# Single_Side_Filter.net
KiCad netlist of a schematic drawn in Altium Designer
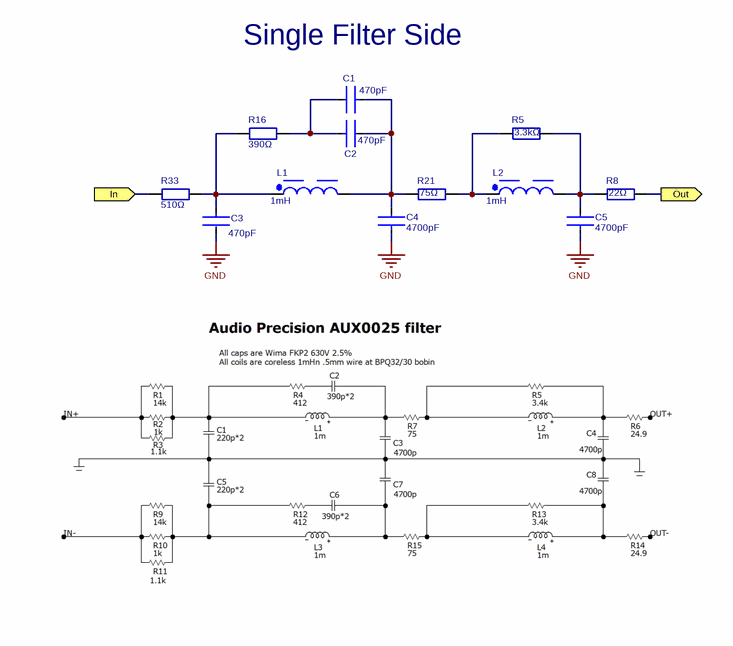
[diagram p0: Single Side Filter.SchDoc]

(export (version "E")
  (design (tool "Eeschema 10.0.6"))
  (components
    (comp (ref "C1")
      (value "470pF")
      (footprint "Film Capacitor 7.2 x 4.5 x 6.0 mm")
      (description "PFR5102F100J11L4BULK Cap Film 0.001uF 100V PP 1% (7.2 X 4.5 X 6mm) Radial 5mm 100C Bulk")
      (fields (field (name "MPN") "FKP2J004701D00HS") (field (name "TOLERANCE") "2.5%"))
      (libsource (lib "Miscellaneous Devices") (part "b4654b650e69147ec39a6b967a45e02"))
    )
    (comp (ref "C2")
      (value "470pF")
      (footprint "Film Capacitor 7.2 x 4.5 x 6.0 mm")
      (description "PFR5102F100J11L4BULK Cap Film 0.001uF 100V PP 1% (7.2 X 4.5 X 6mm) Radial 5mm 100C Bulk")
      (fields (field (name "MPN") "FKP2J004701D00HS") (field (name "TOLERANCE") "2.5%"))
      (libsource (lib "Miscellaneous Devices") (part "b4654b650e69147ec39a6b967a45e02"))
    )
    (comp (ref "C3")
      (value "470pF")
      (footprint "Film Capacitor 7.2 x 4.5 x 6.0 mm")
      (description "PFR5102F100J11L4BULK Cap Film 0.001uF 100V PP 1% (7.2 X 4.5 X 6mm) Radial 5mm 100C Bulk")
      (fields (field (name "MPN") "FKP2J004701D00HS") (field (name "TOLERANCE") "2.5%"))
      (libsource (lib "Miscellaneous Devices") (part "b4654b650e69147ec39a6b967a45e02"))
    )
    (comp (ref "C4")
      (value "4700pF")
      (footprint "Film Capacitor 7.2 x 6.5 x 8.0 mm")
      (description "PFR5102F100J11L4BULK Cap Film 0.001uF 100V PP 1% (7.2 X 4.5 X 6mm) Radial 5mm 100C Bulk")
      (fields (field (name "MPN") "FKP2J014701I00HS") (field (name "TOLERANCE") "2.5%"))
      (libsource (lib "Miscellaneous Devices") (part "b4654b650e69147ec39a6b967a45e02"))
    )
    (comp (ref "C5")
      (value "4700pF")
      (footprint "Film Capacitor 7.2 x 6.5 x 8.0 mm")
      (description "PFR5102F100J11L4BULK Cap Film 0.001uF 100V PP 1% (7.2 X 4.5 X 6mm) Radial 5mm 100C Bulk")
      (fields (field (name "MPN") "FKP2J014701I00HS") (field (name "TOLERANCE") "2.5%"))
      (libsource (lib "Miscellaneous Devices") (part "b4654b650e69147ec39a6b967a45e02"))
    )
    (comp (ref "L1")
      (value "1mH")
      (footprint "WE-PD HV_1210")
      (fields (field (name "MPN") "MSS1278T-105 / 7687709102") (field (name "TOLERANCE") "10%"))
      (libsource (lib "Altium Content Vault") (part "Inductor - 2"))
    )
    (comp (ref "L2")
      (value "1mH")
      (footprint "WE-PD HV_1210")
      (fields (field (name "MPN") "MSS1278T-105 / 7687709102") (field (name "TOLERANCE") "10%"))
      (libsource (lib "Altium Content Vault") (part "Inductor - 2"))
    )
    (comp (ref "R5")
      (value "3.3kΩ")
      (footprint "RESC6432X06N")
      (fields (field (name "TOLERANCE") "1%"))
      (libsource (lib "SchematicLibrary") (part "Res"))
    )
    (comp (ref "R8")
      (value "22Ω")
      (footprint "RESC6432X06N")
      (fields (field (name "TOLERANCE") "1%"))
      (libsource (lib "SchematicLibrary") (part "Res"))
    )
    (comp (ref "R16")
      (value "390Ω")
      (footprint "RESC6432X06N")
      (fields (field (name "TOLERANCE") "1%"))
      (libsource (lib "SchematicLibrary") (part "Res"))
    )
    (comp (ref "R21")
      (value "75Ω")
      (footprint "RESC6432X06N")
      (fields (field (name "TOLERANCE") "1%"))
      (libsource (lib "SchematicLibrary") (part "Res"))
    )
    (comp (ref "R33")
      (value "510Ω")
      (footprint "RESC6432X06N")
      (fields (field (name "TOLERANCE") "1%"))
      (libsource (lib "SchematicLibrary") (part "Res"))
    )
  )
  (nets
    (net (code "1") (name "/In") (class "Default") (node (ref "R33") (pin "1") (pintype "passive")))
    (net (code "2") (name "/Out") (class "Default") (node (ref "R8") (pin "2") (pintype "passive")))
    (net (code "3") (name "GND") (class "Default")
      (node (ref "C3") (pin "2") (pinfunction "2_2") (pintype "passive"))
      (node (ref "C4") (pin "1") (pinfunction "1_1") (pintype "passive"))
      (node (ref "C5") (pin "1") (pinfunction "1_1") (pintype "passive"))
    )
    (net (code "4") (name "Net-(C1-Pad1)") (class "Default")
      (node (ref "C1") (pin "1") (pinfunction "1_1") (pintype "passive"))
      (node (ref "C2") (pin "2") (pinfunction "2_2") (pintype "passive"))
      (node (ref "C4") (pin "2") (pinfunction "2_2") (pintype "passive"))
      (node (ref "L1") (pin "2") (pinfunction "2_2") (pintype "passive"))
      (node (ref "R21") (pin "1") (pintype "passive"))
    )
    (net (code "5") (name "Net-(C1-Pad2)") (class "Default")
      (node (ref "C1") (pin "2") (pinfunction "2_2") (pintype "passive"))
      (node (ref "C2") (pin "1") (pinfunction "1_1") (pintype "passive"))
      (node (ref "R16") (pin "2") (pintype "passive"))
    )
    (net (code "6") (name "Net-(C3-Pad1)") (class "Default")
      (node (ref "C3") (pin "1") (pinfunction "1_1") (pintype "passive"))
      (node (ref "L1") (pin "1") (pinfunction "1_1") (pintype "passive"))
      (node (ref "R16") (pin "1") (pintype "passive"))
      (node (ref "R33") (pin "2") (pintype "passive"))
    )
    (net (code "7") (name "Net-(C5-Pad2)") (class "Default")
      (node (ref "C5") (pin "2") (pinfunction "2_2") (pintype "passive"))
      (node (ref "L2") (pin "2") (pinfunction "2_2") (pintype "passive"))
      (node (ref "R5") (pin "2") (pintype "passive"))
      (node (ref "R8") (pin "1") (pintype "passive"))
    )
    (net (code "8") (name "Net-(L2-Pad1)") (class "Default")
      (node (ref "L2") (pin "1") (pinfunction "1_1") (pintype "passive"))
      (node (ref "R21") (pin "2") (pintype "passive"))
      (node (ref "R5") (pin "1") (pintype "passive"))
    )
  )
)
